# schematic-EasyEDA.net
KiCad netlist of a schematic drawn in EasyEDA
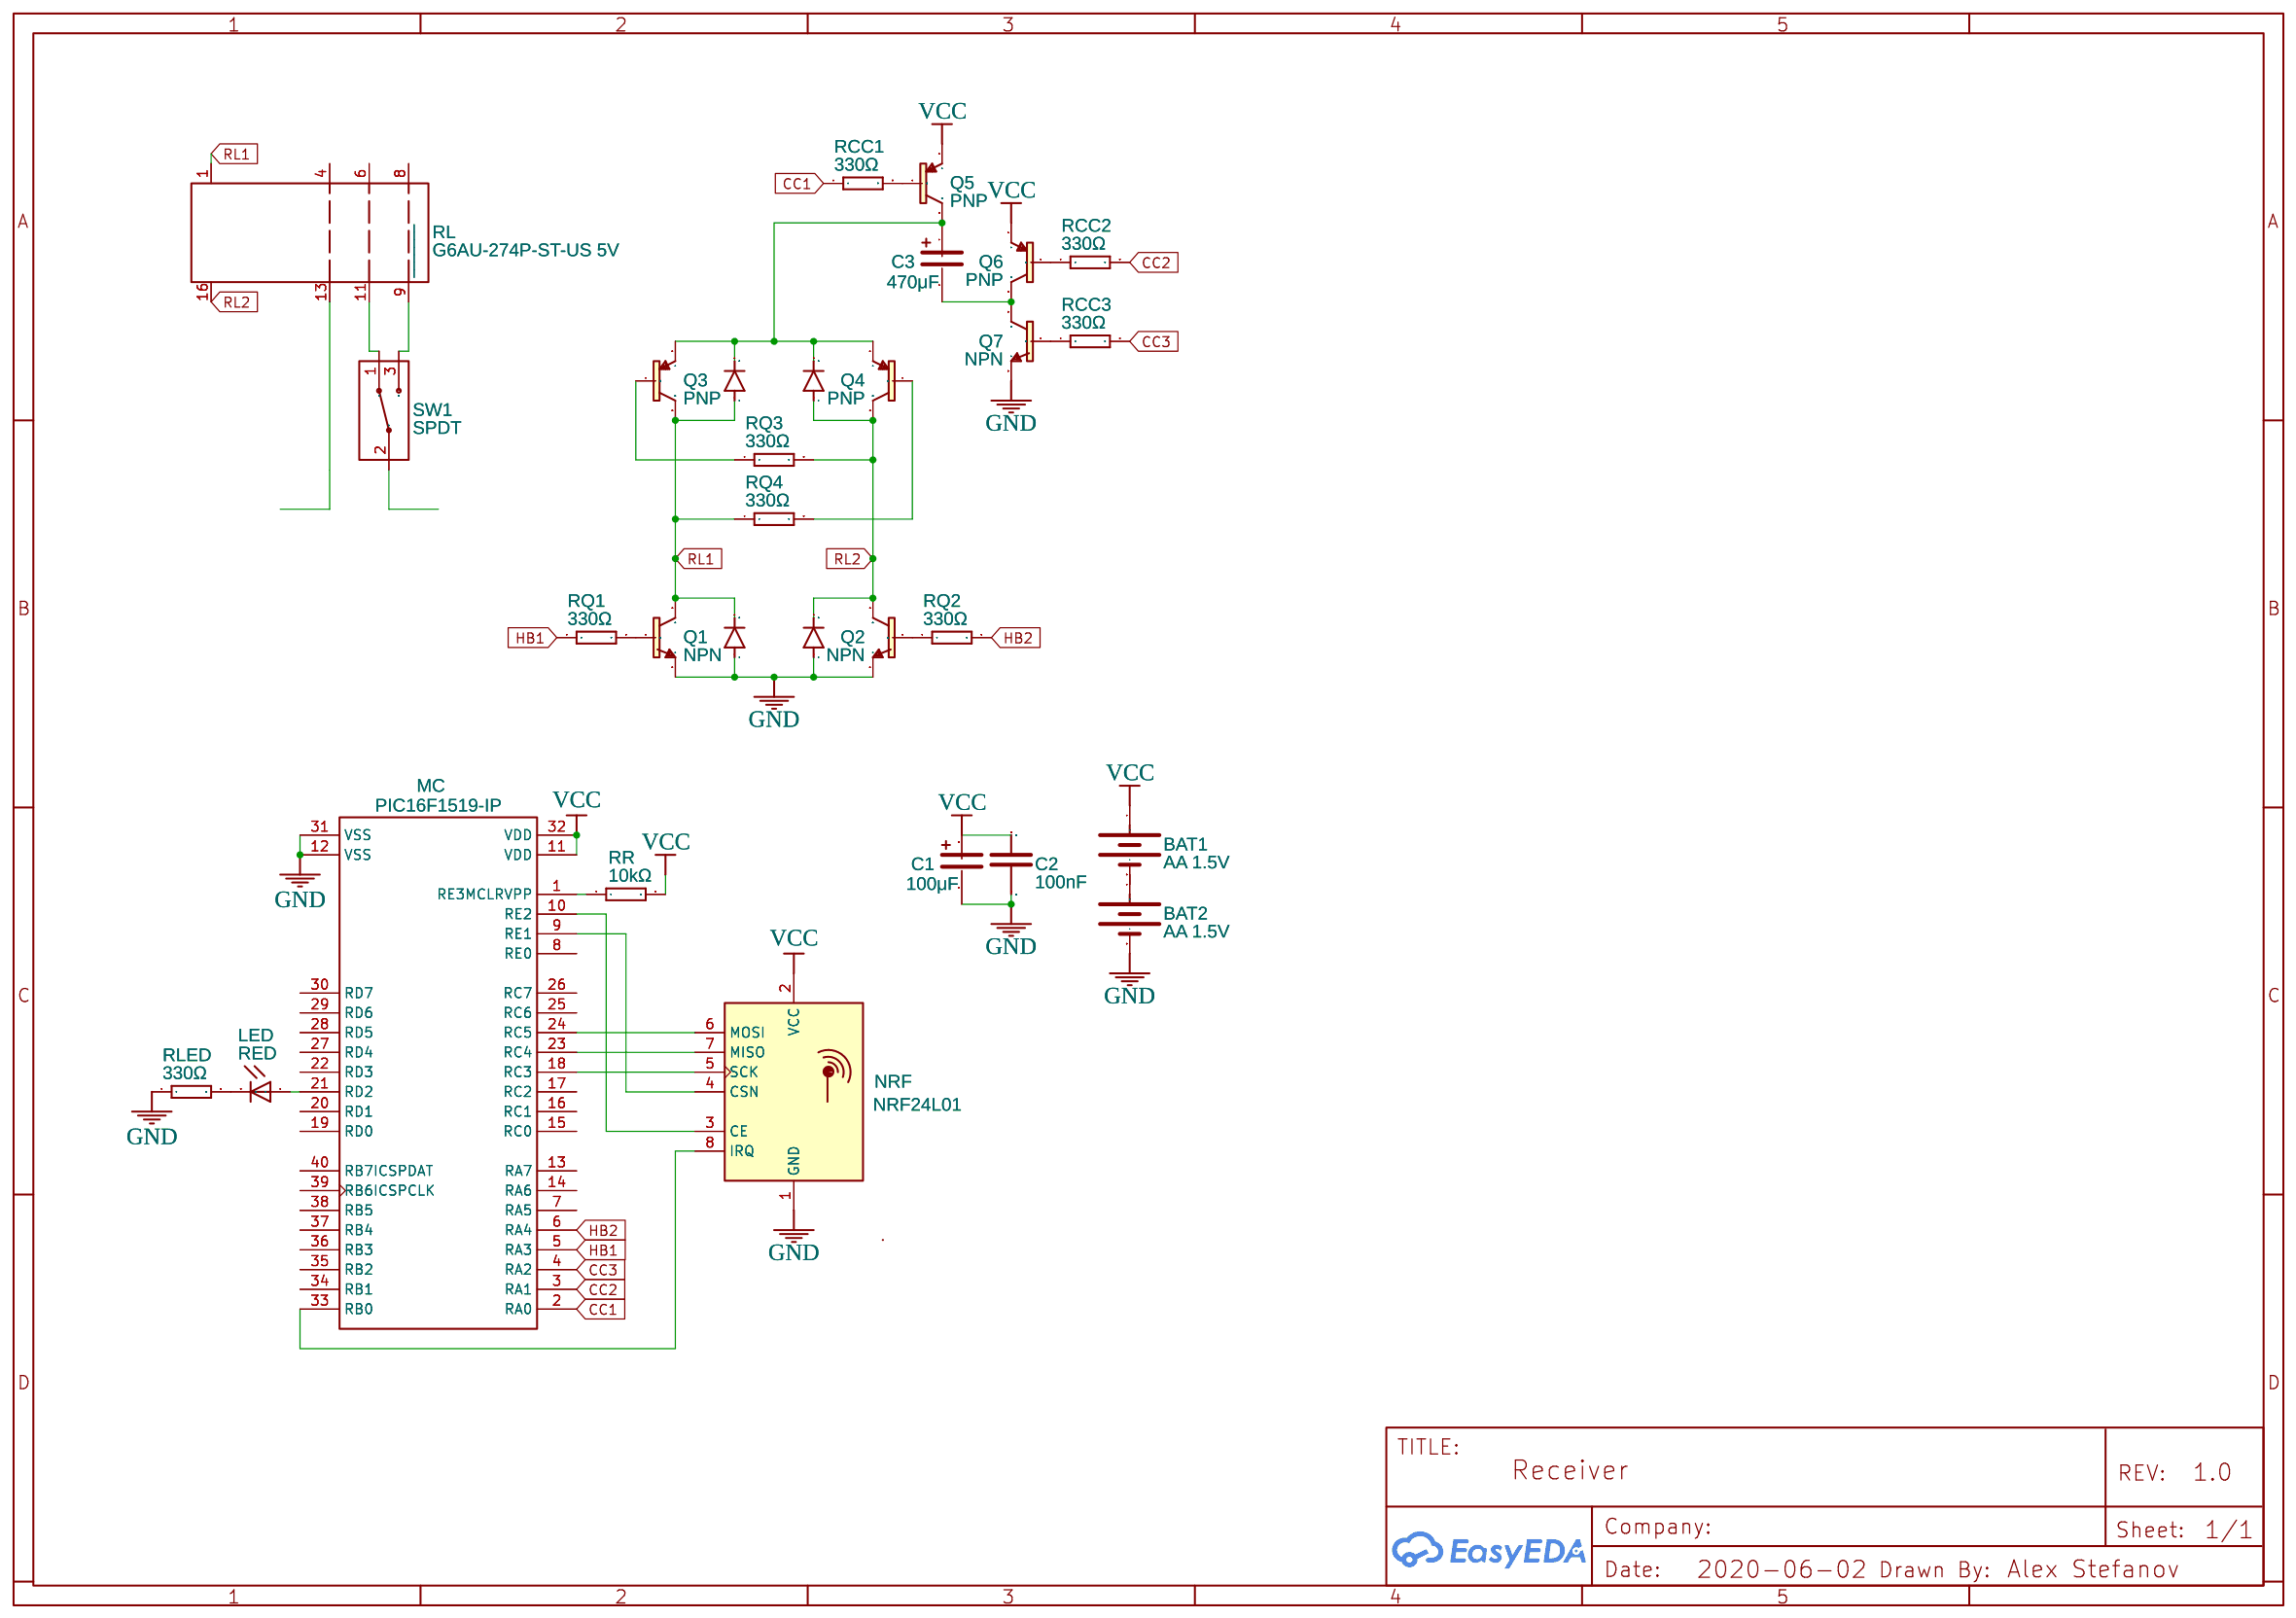
[diagram p0: schematic sheet]

(export (version "E")
  (design (tool "Eeschema 10.0.6"))
  (components
    (comp (ref "BAT1") (value "AA 1.5V") (libsource (lib "") (part "BATTERY")))
    (comp (ref "BAT2") (value "AA 1.5V") (libsource (lib "") (part "BATTERY")))
    (comp (ref "C1")
      (value "100μF")
      (libsource (lib "") (part "Capacitor-Polarized_EN60617-4_04-02-05_Date20121108"))
    )
    (comp (ref "C2") (value "100nF") (libsource (lib "") (part "CAPACITOR")))
    (comp (ref "C3")
      (value "470μF")
      (libsource (lib "") (part "Capacitor-Polarized_EN60617-4_04-02-05_Date20121108"))
    )
    (comp (ref "G") (value "DIODE") (libsource (lib "") (part "DIODE")))
    (comp (ref "G1") (value "DIODE") (libsource (lib "") (part "DIODE")))
    (comp (ref "G2") (value "DIODE") (libsource (lib "") (part "DIODE")))
    (comp (ref "G3") (value "DIODE") (libsource (lib "") (part "DIODE")))
    (comp (ref "LED") (value "RED") (libsource (lib "") (part "LED")))
    (comp (ref "MC") (value "PIC16F1519-IP") (libsource (lib "") (part "PIC16F1519-IP")))
    (comp (ref "NRF") (value "NRF24L01") (libsource (lib "") (part "NRF24L01_Breakout")))
    (comp (ref "Q1") (value "NPN") (libsource (lib "") (part "TRANSISTOR_NPN_1")))
    (comp (ref "Q2") (value "NPN") (libsource (lib "") (part "TRANSISTOR_NPN")))
    (comp (ref "Q3") (value "PNP") (libsource (lib "") (part "TRANSISTOR_PNP_1")))
    (comp (ref "Q4") (value "PNP") (libsource (lib "") (part "TRANSISTOR_PNP")))
    (comp (ref "Q5") (value "PNP") (libsource (lib "") (part "TRANSISTOR_PNP_1")))
    (comp (ref "Q6") (value "PNP") (libsource (lib "") (part "TRANSISTOR_PNP")))
    (comp (ref "Q7") (value "NPN") (libsource (lib "") (part "TRANSISTOR_NPN")))
    (comp (ref "RCC1") (value "330Ω") (libsource (lib "") (part "RESISTOR_2")))
    (comp (ref "RCC2") (value "330Ω") (libsource (lib "") (part "RESISTOR_2")))
    (comp (ref "RCC3") (value "330Ω") (libsource (lib "") (part "RESISTOR_2")))
    (comp (ref "RL")
      (value "G6AU-274P-ST-US 5V")
      (fields
        (field (name "BOM_Manufacturer Part") "RS Pro SPDT PCB Mount Non-Latching Relay, 5V Coil, 20 A Miniature Power Relay")
        (field (name "BOM_Supplier Part") "800-4495")
      )
      (libsource (lib "") (part "RS Pro SPDT PCB Mount Non-Latching Relay, 5V Coil, 20 A Miniature Power Relay"))
    )
    (comp (ref "RLED") (value "330Ω") (libsource (lib "") (part "RESISTOR_1")))
    (comp (ref "RQ1") (value "330Ω") (libsource (lib "") (part "RESISTOR")))
    (comp (ref "RQ2") (value "330Ω") (libsource (lib "") (part "RESISTOR")))
    (comp (ref "RQ3") (value "330Ω") (libsource (lib "") (part "RESISTOR")))
    (comp (ref "RQ4") (value "330Ω") (libsource (lib "") (part "RESISTOR")))
    (comp (ref "RR") (value "10kΩ") (libsource (lib "") (part "RESISTOR_3")))
    (comp (ref "SW1") (value "SPDT") (libsource (lib "") (part "SPDT")))
  )
  (nets
    (net (code "1") (name "CC1") (class "Default")
      (node (ref "MC") (pin "2") (pinfunction "RA0_2") (pintype "bidirectional"))
      (node (ref "RCC1") (pin "1") (pinfunction "1_1") (pintype "unspecified"))
    )
    (net (code "2") (name "CC2") (class "Default")
      (node (ref "MC") (pin "3") (pinfunction "RA1_3") (pintype "bidirectional"))
      (node (ref "RCC2") (pin "2") (pinfunction "2_2") (pintype "unspecified"))
    )
    (net (code "3") (name "CC3") (class "Default")
      (node (ref "MC") (pin "4") (pinfunction "RA2_4") (pintype "bidirectional"))
      (node (ref "RCC3") (pin "2") (pinfunction "2_2") (pintype "unspecified"))
    )
    (net (code "4") (name "GND") (class "Default")
      (node (ref "BAT2") (pin "2") (pinfunction "-_2") (pintype "passive"))
      (node (ref "C1") (pin "2") (pintype "unspecified"))
      (node (ref "C2") (pin "P$2") (pinfunction "P$2_P$2") (pintype "unspecified"))
      (node (ref "G") (pin "A") (pinfunction "A_A") (pintype "bidirectional"))
      (node (ref "G1") (pin "A") (pinfunction "A_A") (pintype "bidirectional"))
      (node (ref "MC") (pin "12") (pinfunction "VSS_12") (pintype "passive"))
      (node (ref "MC") (pin "31") (pinfunction "VSS_31") (pintype "passive"))
      (node (ref "NRF") (pin "1") (pinfunction "GND_1") (pintype "bidirectional"))
      (node (ref "Q1") (pin "2") (pinfunction "E_2") (pintype "unspecified"))
      (node (ref "Q2") (pin "2") (pinfunction "E_2") (pintype "unspecified"))
      (node (ref "Q7") (pin "2") (pinfunction "E_2") (pintype "unspecified"))
      (node (ref "RLED") (pin "1") (pinfunction "1_1") (pintype "unspecified"))
    )
    (net (code "5") (name "HB1") (class "Default")
      (node (ref "MC") (pin "5") (pinfunction "RA3_5") (pintype "bidirectional"))
      (node (ref "RQ1") (pin "1") (pinfunction "1_1") (pintype "unspecified"))
    )
    (net (code "6") (name "HB2") (class "Default")
      (node (ref "MC") (pin "6") (pinfunction "RA4_6") (pintype "bidirectional"))
      (node (ref "RQ2") (pin "2") (pinfunction "2_2") (pintype "unspecified"))
    )
    (net (code "7") (name "Net-(BAT1--)") (class "Default")
      (node (ref "BAT1") (pin "2") (pinfunction "-_2") (pintype "passive"))
      (node (ref "BAT2") (pin "1") (pinfunction "+_1") (pintype "passive"))
    )
    (net (code "8") (name "Net-(LED-PadC)") (class "Default")
      (node (ref "LED") (pin "C") (pinfunction "C_C") (pintype "unspecified"))
      (node (ref "RLED") (pin "2") (pinfunction "2_2") (pintype "unspecified"))
    )
    (net (code "9") (name "Net-(MC-RB0)") (class "Default")
      (node (ref "MC") (pin "33") (pinfunction "RB0_33") (pintype "bidirectional"))
      (node (ref "NRF") (pin "8") (pinfunction "IRQ_8") (pintype "output"))
    )
    (net (code "10") (name "Net-(MC-RC3)") (class "Default")
      (node (ref "MC") (pin "18") (pinfunction "RC3_18") (pintype "bidirectional"))
      (node (ref "NRF") (pin "5") (pinfunction "SCK_5") (pintype "input"))
    )
    (net (code "11") (name "Net-(MC-RC4)") (class "Default")
      (node (ref "MC") (pin "23") (pinfunction "RC4_23") (pintype "bidirectional"))
      (node (ref "NRF") (pin "7") (pinfunction "MISO_7") (pintype "output"))
    )
    (net (code "12") (name "Net-(MC-RC5)") (class "Default")
      (node (ref "MC") (pin "24") (pinfunction "RC5_24") (pintype "bidirectional"))
      (node (ref "NRF") (pin "6") (pinfunction "MOSI_6") (pintype "input"))
    )
    (net (code "13") (name "Net-(MC-RD2)") (class "Default")
      (node (ref "LED") (pin "A") (pinfunction "A_A") (pintype "unspecified"))
      (node (ref "MC") (pin "21") (pinfunction "RD2_21") (pintype "bidirectional"))
    )
    (net (code "14") (name "Net-(MC-RE1)") (class "Default")
      (node (ref "MC") (pin "9") (pinfunction "RE1_9") (pintype "bidirectional"))
      (node (ref "NRF") (pin "4") (pinfunction "CSN_4") (pintype "input"))
    )
    (net (code "15") (name "Net-(MC-RE2)") (class "Default")
      (node (ref "MC") (pin "10") (pinfunction "RE2_10") (pintype "bidirectional"))
      (node (ref "NRF") (pin "3") (pinfunction "CE_3") (pintype "input"))
    )
    (net (code "16") (name "Net-(MC-RE3MCLRVPP)") (class "Default")
      (node (ref "MC") (pin "1") (pinfunction "RE3MCLRVPP_1") (pintype "unspecified"))
      (node (ref "RR") (pin "1") (pinfunction "1_1") (pintype "unspecified"))
    )
    (net (code "17") (name "Net-(Q1-B)") (class "Default")
      (node (ref "Q1") (pin "1") (pinfunction "B_1") (pintype "unspecified"))
      (node (ref "RQ1") (pin "2") (pinfunction "2_2") (pintype "unspecified"))
    )
    (net (code "18") (name "Net-(Q2-B)") (class "Default")
      (node (ref "Q2") (pin "1") (pinfunction "B_1") (pintype "unspecified"))
      (node (ref "RQ2") (pin "1") (pinfunction "1_1") (pintype "unspecified"))
    )
    (net (code "19") (name "Net-(Q3-B)") (class "Default")
      (node (ref "Q3") (pin "1") (pinfunction "B_1") (pintype "unspecified"))
      (node (ref "RQ3") (pin "1") (pinfunction "1_1") (pintype "unspecified"))
    )
    (net (code "20") (name "Net-(Q3-E)") (class "Default")
      (node (ref "C3") (pin "1") (pintype "unspecified"))
      (node (ref "G2") (pin "C") (pinfunction "C_C") (pintype "bidirectional"))
      (node (ref "G3") (pin "C") (pinfunction "C_C") (pintype "bidirectional"))
      (node (ref "Q3") (pin "2") (pinfunction "E_2") (pintype "unspecified"))
      (node (ref "Q4") (pin "2") (pinfunction "E_2") (pintype "unspecified"))
      (node (ref "Q5") (pin "3") (pinfunction "C_3") (pintype "unspecified"))
    )
    (net (code "21") (name "Net-(Q4-B)") (class "Default")
      (node (ref "Q4") (pin "1") (pinfunction "B_1") (pintype "unspecified"))
      (node (ref "RQ4") (pin "2") (pinfunction "2_2") (pintype "unspecified"))
    )
    (net (code "22") (name "Net-(Q5-B)") (class "Default")
      (node (ref "Q5") (pin "1") (pinfunction "B_1") (pintype "unspecified"))
      (node (ref "RCC1") (pin "2") (pinfunction "2_2") (pintype "unspecified"))
    )
    (net (code "23") (name "Net-(Q6-B)") (class "Default")
      (node (ref "Q6") (pin "1") (pinfunction "B_1") (pintype "unspecified"))
      (node (ref "RCC2") (pin "1") (pinfunction "1_1") (pintype "unspecified"))
    )
    (net (code "24") (name "Net-(Q6-C)") (class "Default")
      (node (ref "C3") (pin "2") (pintype "unspecified"))
      (node (ref "Q6") (pin "3") (pinfunction "C_3") (pintype "unspecified"))
      (node (ref "Q7") (pin "3") (pinfunction "C_3") (pintype "unspecified"))
    )
    (net (code "25") (name "Net-(Q7-B)") (class "Default")
      (node (ref "Q7") (pin "1") (pinfunction "B_1") (pintype "unspecified"))
      (node (ref "RCC3") (pin "1") (pinfunction "1_1") (pintype "unspecified"))
    )
    (net (code "26") (name "Net-(RL-Pad11)") (class "Default")
      (node (ref "RL") (pin "11") (pintype "unspecified"))
      (node (ref "SW1") (pin "1") (pinfunction "1_1") (pintype "unspecified"))
    )
    (net (code "27") (name "Net-(RL-_______)") (class "Default")
      (node (ref "RL") (pin "9") (pinfunction "________9") (pintype "unspecified"))
      (node (ref "SW1") (pin "3") (pinfunction "3_3") (pintype "unspecified"))
    )
    (net (code "28") (name "RL1") (class "Default")
      (node (ref "G") (pin "C") (pinfunction "C_C") (pintype "bidirectional"))
      (node (ref "G2") (pin "A") (pinfunction "A_A") (pintype "bidirectional"))
      (node (ref "Q1") (pin "3") (pinfunction "C_3") (pintype "unspecified"))
      (node (ref "Q3") (pin "3") (pinfunction "C_3") (pintype "unspecified"))
      (node (ref "RL") (pin "1") (pintype "unspecified"))
      (node (ref "RQ4") (pin "1") (pinfunction "1_1") (pintype "unspecified"))
    )
    (net (code "29") (name "RL2") (class "Default")
      (node (ref "G1") (pin "C") (pinfunction "C_C") (pintype "bidirectional"))
      (node (ref "G3") (pin "A") (pinfunction "A_A") (pintype "bidirectional"))
      (node (ref "Q2") (pin "3") (pinfunction "C_3") (pintype "unspecified"))
      (node (ref "Q4") (pin "3") (pinfunction "C_3") (pintype "unspecified"))
      (node (ref "RL") (pin "16") (pintype "unspecified"))
      (node (ref "RQ3") (pin "2") (pinfunction "2_2") (pintype "unspecified"))
    )
    (net (code "30") (name "VCC") (class "Default")
      (node (ref "BAT1") (pin "1") (pinfunction "+_1") (pintype "passive"))
      (node (ref "C2") (pin "P$1") (pinfunction "P$1_P$1") (pintype "unspecified"))
      (node (ref "MC") (pin "11") (pinfunction "VDD_11") (pintype "passive"))
      (node (ref "MC") (pin "32") (pinfunction "VDD_32") (pintype "passive"))
      (node (ref "NRF") (pin "2") (pinfunction "VCC_2") (pintype "bidirectional"))
      (node (ref "Q5") (pin "2") (pinfunction "E_2") (pintype "unspecified"))
      (node (ref "Q6") (pin "2") (pinfunction "E_2") (pintype "unspecified"))
      (node (ref "RR") (pin "2") (pinfunction "2_2") (pintype "unspecified"))
    )
    (net (code "31") (name "unconnected-(C1-Pad1)") (class "Default")
      (node (ref "C1") (pin "1") (pintype "unspecified"))
    )
    (net (code "32") (name "unconnected-(MC-RA5-Pad7)") (class "Default")
      (node (ref "MC") (pin "7") (pinfunction "RA5_7") (pintype "bidirectional"))
    )
    (net (code "33") (name "unconnected-(MC-RA6-Pad14)") (class "Default")
      (node (ref "MC") (pin "14") (pinfunction "RA6_14") (pintype "bidirectional"))
    )
    (net (code "34") (name "unconnected-(MC-RA7-Pad13)") (class "Default")
      (node (ref "MC") (pin "13") (pinfunction "RA7_13") (pintype "bidirectional"))
    )
    (net (code "35") (name "unconnected-(MC-RB1-Pad34)") (class "Default")
      (node (ref "MC") (pin "34") (pinfunction "RB1_34") (pintype "bidirectional"))
    )
    (net (code "36") (name "unconnected-(MC-RB2-Pad35)") (class "Default")
      (node (ref "MC") (pin "35") (pinfunction "RB2_35") (pintype "bidirectional"))
    )
    (net (code "37") (name "unconnected-(MC-RB3-Pad36)") (class "Default")
      (node (ref "MC") (pin "36") (pinfunction "RB3_36") (pintype "bidirectional"))
    )
    (net (code "38") (name "unconnected-(MC-RB4-Pad37)") (class "Default")
      (node (ref "MC") (pin "37") (pinfunction "RB4_37") (pintype "bidirectional"))
    )
    (net (code "39") (name "unconnected-(MC-RB5-Pad38)") (class "Default")
      (node (ref "MC") (pin "38") (pinfunction "RB5_38") (pintype "bidirectional"))
    )
    (net (code "40") (name "unconnected-(MC-RB6ICSPCLK-Pad39)") (class "Default")
      (node (ref "MC") (pin "39") (pinfunction "RB6ICSPCLK_39") (pintype "bidirectional"))
    )
    (net (code "41") (name "unconnected-(MC-RB7ICSPDAT-Pad40)") (class "Default")
      (node (ref "MC") (pin "40") (pinfunction "RB7ICSPDAT_40") (pintype "bidirectional"))
    )
    (net (code "42") (name "unconnected-(MC-RC0-Pad15)") (class "Default")
      (node (ref "MC") (pin "15") (pinfunction "RC0_15") (pintype "bidirectional"))
    )
    (net (code "43") (name "unconnected-(MC-RC1-Pad16)") (class "Default")
      (node (ref "MC") (pin "16") (pinfunction "RC1_16") (pintype "bidirectional"))
    )
    (net (code "44") (name "unconnected-(MC-RC2-Pad17)") (class "Default")
      (node (ref "MC") (pin "17") (pinfunction "RC2_17") (pintype "bidirectional"))
    )
    (net (code "45") (name "unconnected-(MC-RC6-Pad25)") (class "Default")
      (node (ref "MC") (pin "25") (pinfunction "RC6_25") (pintype "bidirectional"))
    )
    (net (code "46") (name "unconnected-(MC-RC7-Pad26)") (class "Default")
      (node (ref "MC") (pin "26") (pinfunction "RC7_26") (pintype "bidirectional"))
    )
    (net (code "47") (name "unconnected-(MC-RD0-Pad19)") (class "Default")
      (node (ref "MC") (pin "19") (pinfunction "RD0_19") (pintype "bidirectional"))
    )
    (net (code "48") (name "unconnected-(MC-RD1-Pad20)") (class "Default")
      (node (ref "MC") (pin "20") (pinfunction "RD1_20") (pintype "bidirectional"))
    )
    (net (code "49") (name "unconnected-(MC-RD3-Pad22)") (class "Default")
      (node (ref "MC") (pin "22") (pinfunction "RD3_22") (pintype "bidirectional"))
    )
    (net (code "50") (name "unconnected-(MC-RD4-Pad27)") (class "Default")
      (node (ref "MC") (pin "27") (pinfunction "RD4_27") (pintype "bidirectional"))
    )
    (net (code "51") (name "unconnected-(MC-RD5-Pad28)") (class "Default")
      (node (ref "MC") (pin "28") (pinfunction "RD5_28") (pintype "bidirectional"))
    )
    (net (code "52") (name "unconnected-(MC-RD6-Pad29)") (class "Default")
      (node (ref "MC") (pin "29") (pinfunction "RD6_29") (pintype "bidirectional"))
    )
    (net (code "53") (name "unconnected-(MC-RD7-Pad30)") (class "Default")
      (node (ref "MC") (pin "30") (pinfunction "RD7_30") (pintype "bidirectional"))
    )
    (net (code "54") (name "unconnected-(MC-RE0-Pad8)") (class "Default")
      (node (ref "MC") (pin "8") (pinfunction "RE0_8") (pintype "bidirectional"))
    )
    (net (code "55") (name "unconnected-(RL-Pad4)") (class "Default")
      (node (ref "RL") (pin "4") (pintype "unspecified"))
    )
    (net (code "56") (name "unconnected-(RL-Pad6)") (class "Default")
      (node (ref "RL") (pin "6") (pintype "unspecified"))
    )
    (net (code "57") (name "unconnected-(RL-Pad8)") (class "Default")
      (node (ref "RL") (pin "8") (pintype "unspecified"))
    )
    (net (code "58") (name "unconnected-(RL-Pad13)") (class "Default")
      (node (ref "RL") (pin "13") (pintype "unspecified"))
    )
    (net (code "59") (name "unconnected-(SW1-Pad2)") (class "Default")
      (node (ref "SW1") (pin "2") (pinfunction "2_2") (pintype "unspecified"))
    )
  )
)
